# board2.net
KiCad netlist of a schematic drawn in EAGLE
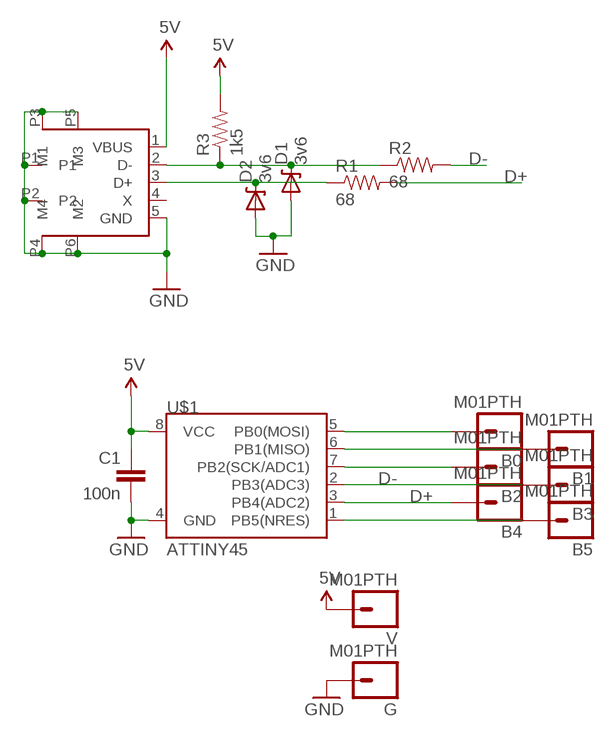
[diagram p0: schematic, sheet 1]

(export (version "E")
  (design (tool "Eeschema 10.0.6"))
  (components
    (comp (ref "B0")
      (value "M01PTH")
      (footprint "eagle-import:1X01")
      (libsource (lib "eagle-import") (part "M01PTH"))
    )
    (comp (ref "B1")
      (value "M01PTH")
      (footprint "eagle-import:1X01")
      (libsource (lib "eagle-import") (part "M01PTH"))
    )
    (comp (ref "B2")
      (value "M01PTH")
      (footprint "eagle-import:1X01")
      (libsource (lib "eagle-import") (part "M01PTH"))
    )
    (comp (ref "B3")
      (value "M01PTH")
      (footprint "eagle-import:1X01")
      (libsource (lib "eagle-import") (part "M01PTH"))
    )
    (comp (ref "B4")
      (value "M01PTH")
      (footprint "eagle-import:1X01")
      (libsource (lib "eagle-import") (part "M01PTH"))
    )
    (comp (ref "B5")
      (value "M01PTH")
      (footprint "eagle-import:1X01")
      (libsource (lib "eagle-import") (part "M01PTH"))
    )
    (comp (ref "C1")
      (value "100n")
      (footprint "eagle-import:0805")
      (libsource (lib "eagle-import") (part "CAP0805"))
    )
    (comp (ref "CON1")
      (value "USBMICRO-FCI")
      (footprint "eagle-import:USBMINIB-10118194-0001LF")
      (libsource (lib "eagle-import") (part "USBMICRO-FCI"))
    )
    (comp (ref "D1")
      (value "3v6")
      (footprint "eagle-import:SOD-323")
      (libsource (lib "eagle-import") (part "DIODE-ZENER-BZT52"))
    )
    (comp (ref "D2")
      (value "3v6")
      (footprint "eagle-import:SOD-323")
      (libsource (lib "eagle-import") (part "DIODE-ZENER-BZT52"))
    )
    (comp (ref "G")
      (value "M01PTH")
      (footprint "eagle-import:1X01")
      (libsource (lib "eagle-import") (part "M01PTH"))
    )
    (comp (ref "R1")
      (value "68")
      (footprint "eagle-import:0805")
      (libsource (lib "eagle-import") (part "RESISTOR0805-RES"))
    )
    (comp (ref "R2")
      (value "68")
      (footprint "eagle-import:0805")
      (libsource (lib "eagle-import") (part "RESISTOR0805-RES"))
    )
    (comp (ref "R3")
      (value "1k5")
      (footprint "eagle-import:0805")
      (libsource (lib "eagle-import") (part "RESISTOR0805-RES"))
    )
    (comp (ref "U$1")
      (value "ATTINY45")
      (footprint "eagle-import:SO08-EIAJ")
      (libsource (lib "eagle-import") (part "ATTINY45"))
    )
    (comp (ref "V")
      (value "M01PTH")
      (footprint "eagle-import:1X01")
      (libsource (lib "eagle-import") (part "M01PTH"))
    )
  )
  (nets
    (net (code "1") (name "/D+") (class "Default")
      (node (ref "B4") (pin "1") (pinfunction "1_1") (pintype "passive"))
      (node (ref "R1") (pin "2") (pinfunction "2_2") (pintype "passive"))
      (node (ref "U$1") (pin "3") (pinfunction "PB4(ADC2)_3") (pintype "bidirectional"))
    )
    (net (code "2") (name "/D-") (class "Default")
      (node (ref "B3") (pin "1") (pinfunction "1_1") (pintype "passive"))
      (node (ref "R2") (pin "2") (pinfunction "2_2") (pintype "passive"))
      (node (ref "U$1") (pin "2") (pinfunction "PB3(ADC3)_2") (pintype "bidirectional"))
    )
    (net (code "3") (name "5V") (class "Default")
      (node (ref "C1") (pin "1") (pinfunction "1_1") (pintype "passive"))
      (node (ref "CON1") (pin "1") (pinfunction "VBUS_1") (pintype "bidirectional"))
      (node (ref "R3") (pin "2") (pinfunction "2_2") (pintype "passive"))
      (node (ref "U$1") (pin "8") (pinfunction "VCC_8") (pintype "bidirectional"))
      (node (ref "V") (pin "1") (pinfunction "1_1") (pintype "passive"))
    )
    (net (code "4") (name "GND") (class "Default")
      (node (ref "C1") (pin "2") (pinfunction "2_2") (pintype "passive"))
      (node (ref "CON1") (pin "5") (pinfunction "GND_5") (pintype "bidirectional"))
      (node (ref "CON1") (pin "P1") (pinfunction "P1_P1") (pintype "bidirectional"))
      (node (ref "CON1") (pin "P2") (pinfunction "P2_P2") (pintype "bidirectional"))
      (node (ref "CON1") (pin "P3") (pinfunction "M1_P3") (pintype "bidirectional"))
      (node (ref "CON1") (pin "P4") (pinfunction "M4_P4") (pintype "bidirectional"))
      (node (ref "CON1") (pin "P5") (pinfunction "M3_P5") (pintype "bidirectional"))
      (node (ref "CON1") (pin "P6") (pinfunction "M2_P6") (pintype "bidirectional"))
      (node (ref "D1") (pin "2") (pinfunction "A_2") (pintype "passive"))
      (node (ref "D2") (pin "2") (pinfunction "A_2") (pintype "passive"))
      (node (ref "G") (pin "1") (pinfunction "1_1") (pintype "passive"))
      (node (ref "U$1") (pin "4") (pinfunction "GND_4") (pintype "bidirectional"))
    )
    (net (code "5") (name "Net-(CON1-D+)") (class "Default")
      (node (ref "CON1") (pin "3") (pinfunction "D+_3") (pintype "bidirectional"))
      (node (ref "D2") (pin "1") (pinfunction "C_1") (pintype "passive"))
      (node (ref "R1") (pin "1") (pinfunction "1_1") (pintype "passive"))
    )
    (net (code "6") (name "Net-(CON1-D-)") (class "Default")
      (node (ref "CON1") (pin "2") (pinfunction "D-_2") (pintype "bidirectional"))
      (node (ref "D1") (pin "1") (pinfunction "C_1") (pintype "passive"))
      (node (ref "R2") (pin "1") (pinfunction "1_1") (pintype "passive"))
      (node (ref "R3") (pin "1") (pinfunction "1_1") (pintype "passive"))
    )
    (net (code "7") (name "Net-(U$1-PB0(MOSI))") (class "Default")
      (node (ref "B0") (pin "1") (pinfunction "1_1") (pintype "passive"))
      (node (ref "U$1") (pin "5") (pinfunction "PB0(MOSI)_5") (pintype "bidirectional"))
    )
    (net (code "8") (name "Net-(U$1-PB1(MISO))") (class "Default")
      (node (ref "B1") (pin "1") (pinfunction "1_1") (pintype "passive"))
      (node (ref "U$1") (pin "6") (pinfunction "PB1(MISO)_6") (pintype "bidirectional"))
    )
    (net (code "9") (name "Net-(U$1-PB2(SCK{slash}ADC1))") (class "Default")
      (node (ref "B2") (pin "1") (pinfunction "1_1") (pintype "passive"))
      (node (ref "U$1") (pin "7") (pinfunction "PB2(SCK/ADC1)_7") (pintype "bidirectional"))
    )
    (net (code "10") (name "Net-(U$1-PB5(NRES))") (class "Default")
      (node (ref "B5") (pin "1") (pinfunction "1_1") (pintype "passive"))
      (node (ref "U$1") (pin "1") (pinfunction "PB5(NRES)_1") (pintype "bidirectional"))
    )
    (net (code "11") (name "unconnected-(CON1-X-Pad4)") (class "Default")
      (node (ref "CON1") (pin "4") (pinfunction "X_4") (pintype "bidirectional"))
    )
  )
)
